# PMON.net
KiCad netlist of a schematic drawn in Altium Designer
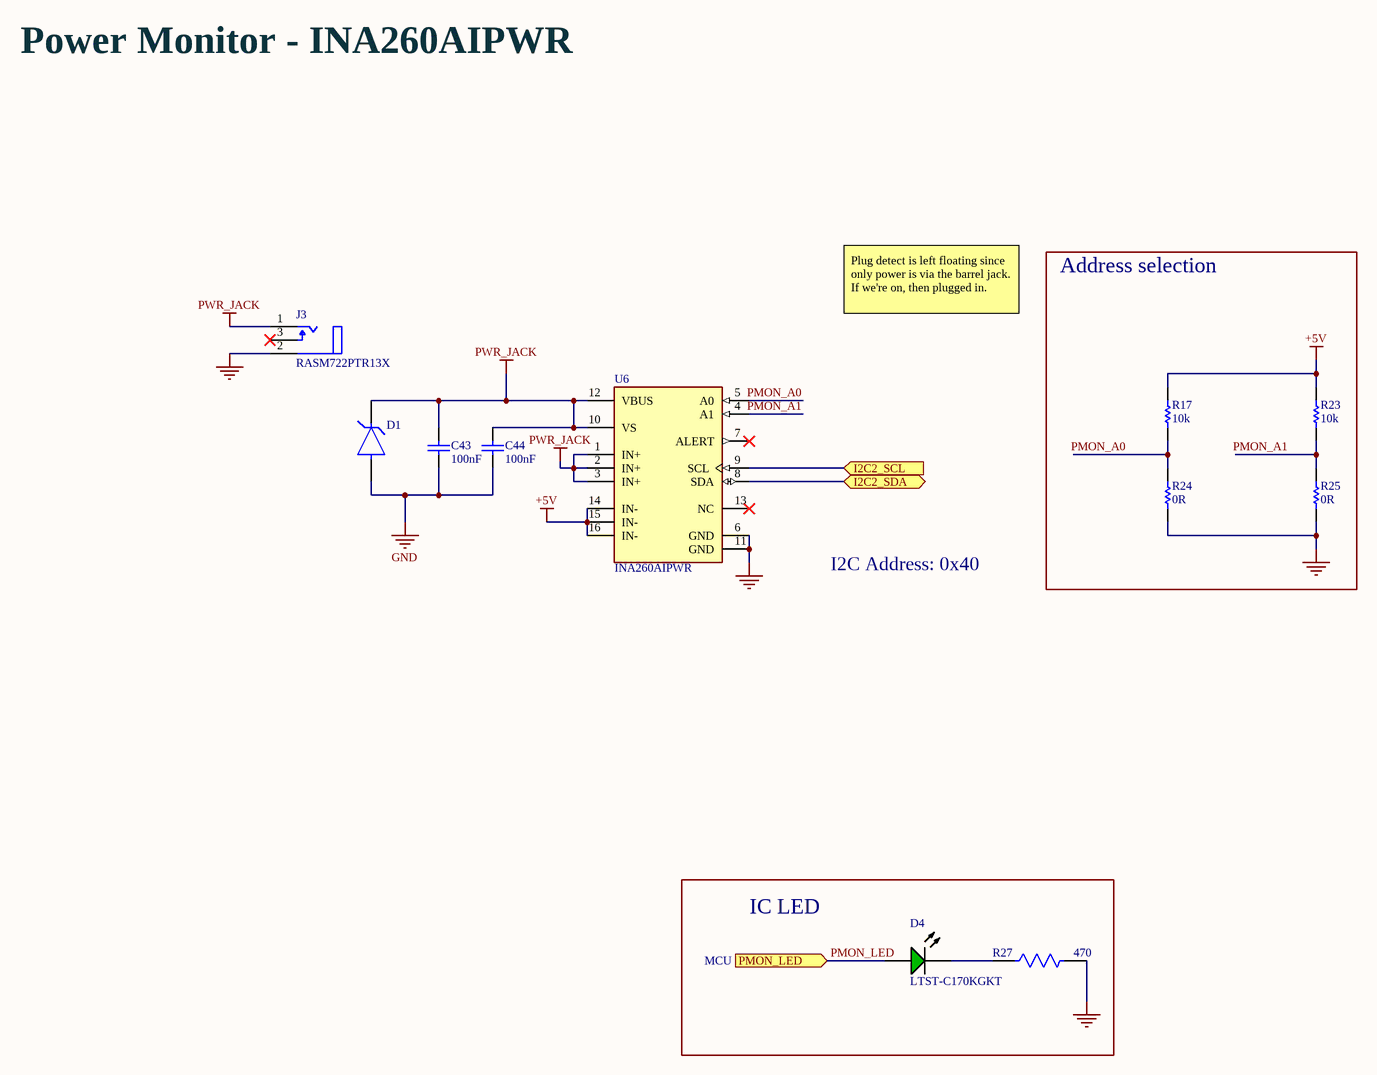
[diagram p0: PMON.SchDoc]

(export (version "E")
  (design (tool "Eeschema 10.0.6"))
  (components
    (comp (ref "C43")
      (value "100nF")
      (footprint "CAPC1005X55X25ML05T10")
      (description "GRM155R60J104KA01D")
      (fields (field (name "MANUFACTURER") "Murata"))
      (libsource (lib "Altium Content Vault") (part "CAP"))
    )
    (comp (ref "C44")
      (value "100nF")
      (footprint "CAPC1005X55X25ML05T10")
      (description "GRM155R60J104KA01D")
      (fields (field (name "MANUFACTURER") "Murata"))
      (libsource (lib "Altium Content Vault") (part "CAP"))
    )
    (comp (ref "D1")
      (value "SMBJ5.0A-TR")
      (footprint "FP-SMB-MFG")
      (description "TVS DIODE 5V 13.4V SMB")
      (fields
        (field (name "MANUFACTURER") "STMicroelectronics")
        (field (name "OCTOPART") "https://octopart.com/smbj5.0a-tr-stmicroelectronics-347079")
      )
      (libsource (lib "Altium Content Vault") (part "7ddec9f632b8482e96f7745d0fbdf39"))
    )
    (comp (ref "D4")
      (value "LTST-C170KGKT")
      (footprint "LTST-LTST-C170KGKT-2_V")
      (description "Ultra Bright AlInGaP Chip LED, 75 mW, -55 to 85 degC, 2-Pin SMD (0805), RoHS, Tape and Reel")
      (fields (field (name "MANUFACTURER") "Lite-On"))
      (libsource (lib "Altium Content Vault") (part "LED-GREEN-KA-2"))
    )
    (comp (ref "J3")
      (value "RASM722PTR13X")
      (footprint "FP-RASM722PTR13X-MFG")
      (description "CONN PWR JACK 2.1X5.5MM SOLDER")
      (libsource (lib "Altium Content Vault") (part "69023cd999ddc70d2a190894d9bbb58"))
    )
    (comp (ref "R17")
      (value "10k")
      (footprint "RESC1608X55X25ML10T15")
      (description "Resistor, 10 KOhm, +/- 5%, 100 mW, -55 to 155 degC, 0603 (1608 Metric), RoHS, Tape and Reel")
      (fields (field (name "MANUFACTURER") "Yageo") (field (name "TOLERANCE") "5%"))
      (libsource (lib "Altium Content Vault") (part "RES-2"))
    )
    (comp (ref "R23")
      (value "10k")
      (footprint "RESC1608X55X25ML10T15")
      (description "Resistor, 10 KOhm, +/- 5%, 100 mW, -55 to 155 degC, 0603 (1608 Metric), RoHS, Tape and Reel")
      (fields (field (name "MANUFACTURER") "Yageo") (field (name "TOLERANCE") "5%"))
      (libsource (lib "Altium Content Vault") (part "RES-2"))
    )
    (comp (ref "R24")
      (value "0R")
      (footprint "RESC1608X55X25ML10T15")
      (description "Chip Resistor, 0 Ohm, +/- 5%, 0.1 W, -55 to 155 degC, 0603 (1608 Metric), RoHS, Tape and Reel")
      (fields (field (name "TOLERANCE") "5%") (field (name "MANUFACTURER") "Yageo"))
      (libsource (lib "Altium Content Vault") (part "RES-2"))
    )
    (comp (ref "R25")
      (value "0R")
      (footprint "RESC1608X55X25ML10T15")
      (description "Chip Resistor, 0 Ohm, +/- 5%, 0.1 W, -55 to 155 degC, 0603 (1608 Metric), RoHS, Tape and Reel")
      (fields (field (name "TOLERANCE") "5%") (field (name "MANUFACTURER") "Yageo"))
      (libsource (lib "Altium Content Vault") (part "RES-2"))
    )
    (comp (ref "R27")
      (value "470")
      (footprint "FP-CPF0603-MFG")
      (description "RES SMD 470Ω 0.1% 1/16W 0603\r\n\r\nCPF0603B470RE")
      (fields
        (field (name "MANUFACTURER") "TE Connectivity")
        (field (name "MANUFACTURER PART NUMBER") "CPF0603B470RE")
      )
      (libsource (lib "Altium Content Vault") (part "1029c3af85768c4190bb7ad29bc67b5"))
    )
    (comp (ref "U6")
      (value "INA260AIPWR")
      (footprint "FP-PW0016A-MFG")
      (description "IC MONITOR PWR/CURR 16TSSOP")
      (fields
        (field (name "MANUFACTURER") "Texas Instruments")
        (field (name "OCTOPART") "https://octopart.com/ina260aipwr-texas+instruments-75199489")
      )
      (libsource (lib "Altium Content Vault") (part "fcceeca0fd405d0f0207f40a7ff7922"))
    )
  )
  (nets
    (net (code "1") (name "+5V") (class "Default")
      (node (ref "R17") (pin "2") (pinfunction "2_2") (pintype "passive"))
      (node (ref "R23") (pin "2") (pinfunction "2_2") (pintype "passive"))
      (node (ref "U6") (pin "14") (pinfunction "IN-_14") (pintype "passive"))
      (node (ref "U6") (pin "15") (pinfunction "IN-_15") (pintype "passive"))
      (node (ref "U6") (pin "16") (pinfunction "IN-_16") (pintype "passive"))
    )
    (net (code "2") (name "/I2C2_SCL") (class "Default")
      (node (ref "U6") (pin "9") (pinfunction "SCL_9") (pintype "input"))
    )
    (net (code "3") (name "/I2C2_SDA") (class "Default")
      (node (ref "U6") (pin "8") (pinfunction "SDA_8") (pintype "bidirectional"))
    )
    (net (code "4") (name "/PMON_A0") (class "Default")
      (node (ref "R17") (pin "1") (pinfunction "1_1") (pintype "passive"))
      (node (ref "R24") (pin "2") (pinfunction "2_2") (pintype "passive"))
      (node (ref "U6") (pin "5") (pinfunction "A0_5") (pintype "input"))
    )
    (net (code "5") (name "/PMON_A1") (class "Default")
      (node (ref "R23") (pin "1") (pinfunction "1_1") (pintype "passive"))
      (node (ref "R25") (pin "2") (pinfunction "2_2") (pintype "passive"))
      (node (ref "U6") (pin "4") (pinfunction "A1_4") (pintype "input"))
    )
    (net (code "6") (name "/PMON_LED") (class "Default")
      (node (ref "D4") (pin "2") (pinfunction "A_2") (pintype "passive"))
    )
    (net (code "7") (name "GND") (class "Default")
      (node (ref "C43") (pin "1") (pinfunction "1_1") (pintype "passive"))
      (node (ref "C44") (pin "1") (pinfunction "1_1") (pintype "passive"))
      (node (ref "D1") (pin "2") (pinfunction "A_2") (pintype "passive"))
      (node (ref "J3") (pin "2") (pinfunction "SLEEVE_TERMINAL_2") (pintype "passive"))
      (node (ref "R24") (pin "1") (pinfunction "1_1") (pintype "passive"))
      (node (ref "R25") (pin "1") (pinfunction "1_1") (pintype "passive"))
      (node (ref "R27") (pin "2") (pinfunction "2_2") (pintype "passive"))
      (node (ref "U6") (pin "11") (pinfunction "GND_11") (pintype "power_in"))
      (node (ref "U6") (pin "6") (pinfunction "GND_6") (pintype "power_in"))
    )
    (net (code "8") (name "Net-(D4-K)") (class "Default")
      (node (ref "D4") (pin "1") (pinfunction "K_1") (pintype "passive"))
      (node (ref "R27") (pin "1") (pinfunction "1_1") (pintype "passive"))
    )
    (net (code "9") (name "PWR_JACK") (class "Default")
      (node (ref "C43") (pin "2") (pinfunction "2_2") (pintype "passive"))
      (node (ref "C44") (pin "2") (pinfunction "2_2") (pintype "passive"))
      (node (ref "D1") (pin "1") (pinfunction "K_1") (pintype "passive"))
      (node (ref "J3") (pin "1") (pinfunction "TIP_TERMINAL(CENTER_PIN)_1") (pintype "passive"))
      (node (ref "U6") (pin "1") (pinfunction "IN+_1") (pintype "passive"))
      (node (ref "U6") (pin "10") (pinfunction "VS_10") (pintype "passive"))
      (node (ref "U6") (pin "12") (pinfunction "VBUS_12") (pintype "passive"))
      (node (ref "U6") (pin "2") (pinfunction "IN+_2") (pintype "passive"))
      (node (ref "U6") (pin "3") (pinfunction "IN+_3") (pintype "passive"))
    )
    (net (code "10") (name "unconnected-(J3-SHUNT_TERMINAL-Pad3)") (class "Default")
      (node (ref "J3") (pin "3") (pinfunction "SHUNT_TERMINAL_3") (pintype "passive+no_connect"))
    )
    (net (code "11") (name "unconnected-(U6-ALERT-Pad7)") (class "Default")
      (node (ref "U6") (pin "7") (pinfunction "ALERT_7") (pintype "output+no_connect"))
    )
    (net (code "12") (name "unconnected-(U6-NC-Pad13)") (class "Default")
      (node (ref "U6") (pin "13") (pinfunction "NC_13") (pintype "passive+no_connect"))
    )
  )
)
